# micron_P8.net
KiCad netlist of a schematic drawn in Altium Designer
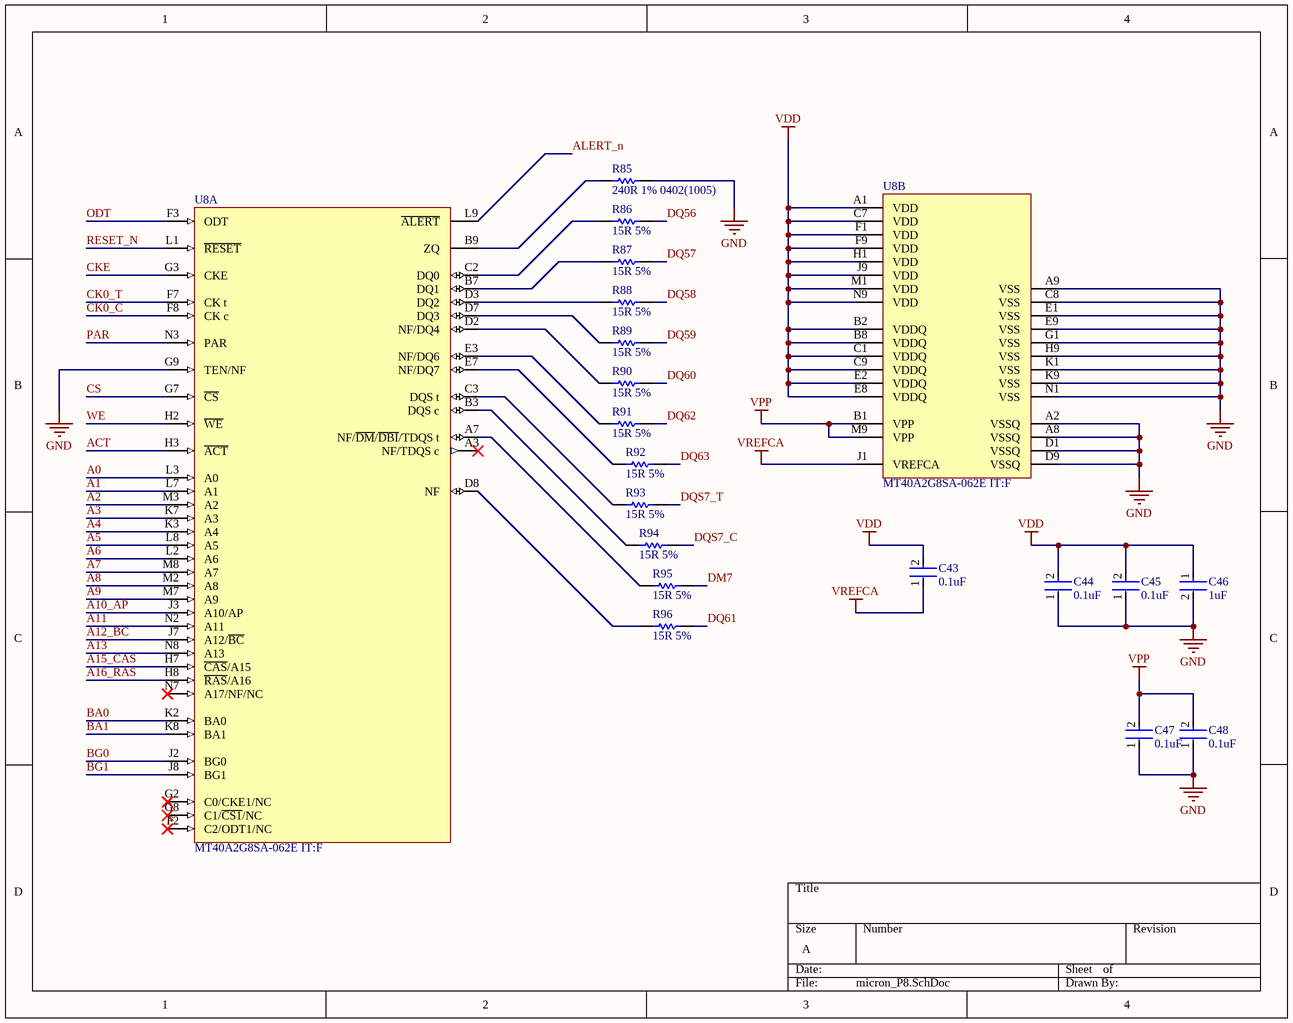
[diagram p0: micron_P8.SchDoc]

(export (version "E")
  (design (tool "Eeschema 10.0.6"))
  (components
    (comp (ref "C43")
      (value "0.1uF")
      (footprint "FP-GRM15-MFG")
      (description "CAP CER 0.1UF 16V X7R 0402")
      (fields (field (name "MANUFACTURER PART NUMBER") "GRM155R71C104KA88D") (field (name "TOLERANCE") "10%"))
      (libsource (lib "Altium Content Vault") (part "236180d848d6139a670b325ea6854c9"))
    )
    (comp (ref "C44")
      (value "0.1uF")
      (footprint "FP-GRM15-MFG")
      (description "CAP CER 0.1UF 16V X7R 0402")
      (fields (field (name "MANUFACTURER PART NUMBER") "GRM155R71C104KA88D") (field (name "TOLERANCE") "10%"))
      (libsource (lib "Altium Content Vault") (part "236180d848d6139a670b325ea6854c9"))
    )
    (comp (ref "C45")
      (value "0.1uF")
      (footprint "FP-GRM15-MFG")
      (description "CAP CER 0.1UF 16V X7R 0402")
      (fields (field (name "MANUFACTURER PART NUMBER") "GRM155R71C104KA88D") (field (name "TOLERANCE") "10%"))
      (libsource (lib "Altium Content Vault") (part "236180d848d6139a670b325ea6854c9"))
    )
    (comp (ref "C46")
      (value "1uF")
      (footprint "FP-CL511-IPC_C")
      (description "Cap Ceramic 1uF 10V X5R ±10% SMD 0402 +85°C Paper T/R")
      (fields (field (name "TOLERANCE") "10%"))
      (libsource (lib "Altium Content Vault") (part "b4654b650e69147ec39a6b967a45e02"))
    )
    (comp (ref "C47")
      (value "0.1uF")
      (footprint "FP-GRM15-MFG")
      (description "CAP CER 0.1UF 16V X7R 0402")
      (fields (field (name "MANUFACTURER PART NUMBER") "GRM155R71C104KA88D") (field (name "TOLERANCE") "10%"))
      (libsource (lib "Altium Content Vault") (part "236180d848d6139a670b325ea6854c9"))
    )
    (comp (ref "C48")
      (value "0.1uF")
      (footprint "FP-GRM15-MFG")
      (description "CAP CER 0.1UF 16V X7R 0402")
      (fields (field (name "MANUFACTURER PART NUMBER") "GRM155R71C104KA88D") (field (name "TOLERANCE") "10%"))
      (libsource (lib "Altium Content Vault") (part "236180d848d6139a670b325ea6854c9"))
    )
    (comp (ref "R85")
      (value "240R 1% 0402(1005)")
      (footprint "RESC0402(1005)_L")
      (description "240R 0.063W 1% 0402 (1005 Metric)  SMD")
      (fields (field (name "POWER") "0.063 W") (field (name "TOLERANCE") "1 %"))
      (libsource (lib "Altium Content Vault") (part "RES"))
    )
    (comp (ref "R86")
      (value "15R 5%")
      (footprint "RESC1005X40X25LL05T10")
      (fields (field (name "MANUFACTURER") "Yageo / Phycomp") (field (name "PART NUMBER") "RC0402FR-0715RL"))
      (libsource (lib "Altium Content Vault") (part "RES"))
    )
    (comp (ref "R87")
      (value "15R 5%")
      (footprint "RESC1005X40X25LL05T10")
      (fields (field (name "MANUFACTURER") "Yageo / Phycomp") (field (name "PART NUMBER") "RC0402FR-0715RL"))
      (libsource (lib "Altium Content Vault") (part "RES"))
    )
    (comp (ref "R88")
      (value "15R 5%")
      (footprint "RESC1005X40X25LL05T10")
      (fields (field (name "MANUFACTURER") "Yageo / Phycomp") (field (name "PART NUMBER") "RC0402FR-0715RL"))
      (libsource (lib "Altium Content Vault") (part "RES"))
    )
    (comp (ref "R89")
      (value "15R 5%")
      (footprint "RESC1005X40X25LL05T10")
      (fields (field (name "MANUFACTURER") "Yageo / Phycomp") (field (name "PART NUMBER") "RC0402FR-0715RL"))
      (libsource (lib "Altium Content Vault") (part "RES"))
    )
    (comp (ref "R90")
      (value "15R 5%")
      (footprint "RESC1005X40X25LL05T10")
      (fields (field (name "MANUFACTURER") "Yageo / Phycomp") (field (name "PART NUMBER") "RC0402FR-0715RL"))
      (libsource (lib "Altium Content Vault") (part "RES"))
    )
    (comp (ref "R91")
      (value "15R 5%")
      (footprint "RESC1005X40X25LL05T10")
      (fields (field (name "MANUFACTURER") "Yageo / Phycomp") (field (name "PART NUMBER") "RC0402FR-0715RL"))
      (libsource (lib "Altium Content Vault") (part "RES"))
    )
    (comp (ref "R92")
      (value "15R 5%")
      (footprint "RESC1005X40X25LL05T10")
      (fields (field (name "MANUFACTURER") "Yageo / Phycomp") (field (name "PART NUMBER") "RC0402FR-0715RL"))
      (libsource (lib "Altium Content Vault") (part "RES"))
    )
    (comp (ref "R93")
      (value "15R 5%")
      (footprint "RESC1005X40X25LL05T10")
      (fields (field (name "MANUFACTURER") "Yageo / Phycomp") (field (name "PART NUMBER") "RC0402FR-0715RL"))
      (libsource (lib "Altium Content Vault") (part "RES"))
    )
    (comp (ref "R94")
      (value "15R 5%")
      (footprint "RESC1005X40X25LL05T10")
      (fields (field (name "MANUFACTURER") "Yageo / Phycomp") (field (name "PART NUMBER") "RC0402FR-0715RL"))
      (libsource (lib "Altium Content Vault") (part "RES"))
    )
    (comp (ref "R95")
      (value "15R 5%")
      (footprint "RESC1005X40X25LL05T10")
      (fields (field (name "MANUFACTURER") "Yageo / Phycomp") (field (name "PART NUMBER") "RC0402FR-0715RL"))
      (libsource (lib "Altium Content Vault") (part "RES"))
    )
    (comp (ref "R96")
      (value "15R 5%")
      (footprint "RESC1005X40X25LL05T10")
      (fields (field (name "MANUFACTURER") "Yageo / Phycomp") (field (name "PART NUMBER") "RC0402FR-0715RL"))
      (libsource (lib "Altium Content Vault") (part "RES"))
    )
    (comp (ref "U8")
      (value "MT40A2G8SA-062E IT:F")
      (footprint "SA_MFG")
      (description "DRAMChip DDR4 SDRAM 16Gbit 2Gx8 1.2V 78-Pin FBGA Tray")
      (libsource (lib "Altium Content Vault") (part "d28cb998757b614ee3280f10a38a3b1"))
    )
  )
  (nets
    (net (code "1") (name "/A0") (class "Default")
      (node (ref "U8") (pin "L3") (pinfunction "A0_L3") (pintype "input"))
    )
    (net (code "2") (name "/A1") (class "Default")
      (node (ref "U8") (pin "L7") (pinfunction "A1_L7") (pintype "input"))
    )
    (net (code "3") (name "/A2") (class "Default")
      (node (ref "U8") (pin "M3") (pinfunction "A2_M3") (pintype "input"))
    )
    (net (code "4") (name "/A3") (class "Default")
      (node (ref "U8") (pin "K7") (pinfunction "A3_K7") (pintype "input"))
    )
    (net (code "5") (name "/A4") (class "Default")
      (node (ref "U8") (pin "K3") (pinfunction "A4_K3") (pintype "input"))
    )
    (net (code "6") (name "/A5") (class "Default")
      (node (ref "U8") (pin "L8") (pinfunction "A5_L8") (pintype "input"))
    )
    (net (code "7") (name "/A6") (class "Default")
      (node (ref "U8") (pin "L2") (pinfunction "A6_L2") (pintype "input"))
    )
    (net (code "8") (name "/A7") (class "Default")
      (node (ref "U8") (pin "M8") (pinfunction "A7_M8") (pintype "input"))
    )
    (net (code "9") (name "/A8") (class "Default")
      (node (ref "U8") (pin "M2") (pinfunction "A8_M2") (pintype "input"))
    )
    (net (code "10") (name "/A9") (class "Default")
      (node (ref "U8") (pin "M7") (pinfunction "A9_M7") (pintype "input"))
    )
    (net (code "11") (name "/A10_AP") (class "Default")
      (node (ref "U8") (pin "J3") (pinfunction "A10/AP_J3") (pintype "input"))
    )
    (net (code "12") (name "/A11") (class "Default")
      (node (ref "U8") (pin "N2") (pinfunction "A11_N2") (pintype "input"))
    )
    (net (code "13") (name "/A12_BC") (class "Default")
      (node (ref "U8") (pin "J7") (pinfunction "A12/~{BC}_J7") (pintype "input"))
    )
    (net (code "14") (name "/A13") (class "Default")
      (node (ref "U8") (pin "N8") (pinfunction "A13_N8") (pintype "input"))
    )
    (net (code "15") (name "/A15_CAS") (class "Default")
      (node (ref "U8") (pin "H7") (pinfunction "~{CAS}/A15_H7") (pintype "input"))
    )
    (net (code "16") (name "/A16_RAS") (class "Default")
      (node (ref "U8") (pin "H8") (pinfunction "~{RAS}/A16_H8") (pintype "input"))
    )
    (net (code "17") (name "/ACT") (class "Default")
      (node (ref "U8") (pin "H3") (pinfunction "~{ACT}_H3") (pintype "input"))
    )
    (net (code "18") (name "/ALERT_n") (class "Default")
      (node (ref "U8") (pin "L9") (pinfunction "~{ALERT}_L9") (pintype "open_collector"))
    )
    (net (code "19") (name "/BA0") (class "Default")
      (node (ref "U8") (pin "K2") (pinfunction "BA0_K2") (pintype "input"))
    )
    (net (code "20") (name "/BA1") (class "Default")
      (node (ref "U8") (pin "K8") (pinfunction "BA1_K8") (pintype "input"))
    )
    (net (code "21") (name "/BG0") (class "Default")
      (node (ref "U8") (pin "J2") (pinfunction "BG0_J2") (pintype "input"))
    )
    (net (code "22") (name "/BG1") (class "Default")
      (node (ref "U8") (pin "J8") (pinfunction "BG1_J8") (pintype "input"))
    )
    (net (code "23") (name "/CK0_C") (class "Default")
      (node (ref "U8") (pin "F8") (pinfunction "CK_c_F8") (pintype "input"))
    )
    (net (code "24") (name "/CK0_T") (class "Default")
      (node (ref "U8") (pin "F7") (pinfunction "CK_t_F7") (pintype "input"))
    )
    (net (code "25") (name "/CKE") (class "Default")
      (node (ref "U8") (pin "G3") (pinfunction "CKE_G3") (pintype "input"))
    )
    (net (code "26") (name "/CS") (class "Default")
      (node (ref "U8") (pin "G7") (pinfunction "~{CS}_G7") (pintype "input"))
    )
    (net (code "27") (name "/DM7") (class "Default")
      (node (ref "R95") (pin "2") (pinfunction "2_2") (pintype "passive"))
    )
    (net (code "28") (name "/DQ56") (class "Default")
      (node (ref "R86") (pin "2") (pinfunction "2_2") (pintype "passive"))
    )
    (net (code "29") (name "/DQ57") (class "Default")
      (node (ref "R87") (pin "2") (pinfunction "2_2") (pintype "passive"))
    )
    (net (code "30") (name "/DQ58") (class "Default")
      (node (ref "R88") (pin "2") (pinfunction "2_2") (pintype "passive"))
    )
    (net (code "31") (name "/DQ59") (class "Default")
      (node (ref "R89") (pin "2") (pinfunction "2_2") (pintype "passive"))
    )
    (net (code "32") (name "/DQ60") (class "Default")
      (node (ref "R90") (pin "2") (pinfunction "2_2") (pintype "passive"))
    )
    (net (code "33") (name "/DQ61") (class "Default")
      (node (ref "R96") (pin "2") (pinfunction "2_2") (pintype "passive"))
    )
    (net (code "34") (name "/DQ62") (class "Default")
      (node (ref "R91") (pin "2") (pinfunction "2_2") (pintype "passive"))
    )
    (net (code "35") (name "/DQ63") (class "Default")
      (node (ref "R92") (pin "2") (pinfunction "2_2") (pintype "passive"))
    )
    (net (code "36") (name "/DQS7_C") (class "Default")
      (node (ref "R94") (pin "2") (pinfunction "2_2") (pintype "passive"))
    )
    (net (code "37") (name "/DQS7_T") (class "Default")
      (node (ref "R93") (pin "2") (pinfunction "2_2") (pintype "passive"))
    )
    (net (code "38") (name "/ODT") (class "Default")
      (node (ref "U8") (pin "F3") (pinfunction "ODT_F3") (pintype "input"))
    )
    (net (code "39") (name "/PAR") (class "Default")
      (node (ref "U8") (pin "N3") (pinfunction "PAR_N3") (pintype "input"))
    )
    (net (code "40") (name "/RESET_N") (class "Default")
      (node (ref "U8") (pin "L1") (pinfunction "~{RESET}_L1") (pintype "input"))
    )
    (net (code "41") (name "/WE") (class "Default")
      (node (ref "U8") (pin "H2") (pinfunction "~{WE}_H2") (pintype "input"))
    )
    (net (code "42") (name "GND") (class "Default")
      (node (ref "C44") (pin "1") (pinfunction "1_1") (pintype "passive"))
      (node (ref "C45") (pin "1") (pinfunction "1_1") (pintype "passive"))
      (node (ref "C46") (pin "2") (pinfunction "2_2") (pintype "passive"))
      (node (ref "C47") (pin "1") (pinfunction "1_1") (pintype "passive"))
      (node (ref "C48") (pin "1") (pinfunction "1_1") (pintype "passive"))
      (node (ref "R85") (pin "2") (pinfunction "2_2") (pintype "passive"))
      (node (ref "U8") (pin "A2") (pinfunction "VSSQ_A2") (pintype "power_in"))
      (node (ref "U8") (pin "A8") (pinfunction "VSSQ_A8") (pintype "power_in"))
      (node (ref "U8") (pin "A9") (pinfunction "VSS_A9") (pintype "power_in"))
      (node (ref "U8") (pin "C8") (pinfunction "VSS_C8") (pintype "power_in"))
      (node (ref "U8") (pin "D1") (pinfunction "VSSQ_D1") (pintype "power_in"))
      (node (ref "U8") (pin "D9") (pinfunction "VSSQ_D9") (pintype "power_in"))
      (node (ref "U8") (pin "E1") (pinfunction "VSS_E1") (pintype "power_in"))
      (node (ref "U8") (pin "E9") (pinfunction "VSS_E9") (pintype "power_in"))
      (node (ref "U8") (pin "G1") (pinfunction "VSS_G1") (pintype "power_in"))
      (node (ref "U8") (pin "G9") (pinfunction "TEN/NF_G9") (pintype "input"))
      (node (ref "U8") (pin "H9") (pinfunction "VSS_H9") (pintype "power_in"))
      (node (ref "U8") (pin "K1") (pinfunction "VSS_K1") (pintype "power_in"))
      (node (ref "U8") (pin "K9") (pinfunction "VSS_K9") (pintype "power_in"))
      (node (ref "U8") (pin "N1") (pinfunction "VSS_N1") (pintype "power_in"))
    )
    (net (code "43") (name "Net-(U8A-DQ0)") (class "Default")
      (node (ref "R86") (pin "1") (pinfunction "1_1") (pintype "passive"))
      (node (ref "U8") (pin "C2") (pinfunction "DQ0_C2") (pintype "bidirectional"))
    )
    (net (code "44") (name "Net-(U8A-DQ1)") (class "Default")
      (node (ref "R87") (pin "1") (pinfunction "1_1") (pintype "passive"))
      (node (ref "U8") (pin "B7") (pinfunction "DQ1_B7") (pintype "bidirectional"))
    )
    (net (code "45") (name "Net-(U8A-DQ2)") (class "Default")
      (node (ref "R88") (pin "1") (pinfunction "1_1") (pintype "passive"))
      (node (ref "U8") (pin "D3") (pinfunction "DQ2_D3") (pintype "bidirectional"))
    )
    (net (code "46") (name "Net-(U8A-DQ3)") (class "Default")
      (node (ref "R89") (pin "1") (pinfunction "1_1") (pintype "passive"))
      (node (ref "U8") (pin "D7") (pinfunction "DQ3_D7") (pintype "bidirectional"))
    )
    (net (code "47") (name "Net-(U8A-DQS_c)") (class "Default")
      (node (ref "R94") (pin "1") (pinfunction "1_1") (pintype "passive"))
      (node (ref "U8") (pin "B3") (pinfunction "DQS_c_B3") (pintype "bidirectional"))
    )
    (net (code "48") (name "Net-(U8A-DQS_t)") (class "Default")
      (node (ref "R93") (pin "1") (pinfunction "1_1") (pintype "passive"))
      (node (ref "U8") (pin "C3") (pinfunction "DQS_t_C3") (pintype "bidirectional"))
    )
    (net (code "49") (name "Net-(U8A-NF)") (class "Default")
      (node (ref "R96") (pin "1") (pinfunction "1_1") (pintype "passive"))
      (node (ref "U8") (pin "D8") (pinfunction "NF_D8") (pintype "bidirectional"))
    )
    (net (code "50") (name "Net-(U8A-NF{slash}DQ4)") (class "Default")
      (node (ref "R90") (pin "1") (pinfunction "1_1") (pintype "passive"))
      (node (ref "U8") (pin "D2") (pinfunction "NF/DQ4_D2") (pintype "bidirectional"))
    )
    (net (code "51") (name "Net-(U8A-NF{slash}DQ6)") (class "Default")
      (node (ref "R91") (pin "1") (pinfunction "1_1") (pintype "passive"))
      (node (ref "U8") (pin "E3") (pinfunction "NF/DQ6_E3") (pintype "bidirectional"))
    )
    (net (code "52") (name "Net-(U8A-NF{slash}DQ7)") (class "Default")
      (node (ref "R92") (pin "1") (pinfunction "1_1") (pintype "passive"))
      (node (ref "U8") (pin "E7") (pinfunction "NF/DQ7_E7") (pintype "bidirectional"))
    )
    (net (code "53") (name "Net-(U8A-NF{slash}~{DM}{slash}~{DBI}{slash}TDQS_t)") (class "Default")
      (node (ref "R95") (pin "1") (pinfunction "1_1") (pintype "passive"))
      (node (ref "U8") (pin "A7") (pinfunction "NF/~{DM}/~{DBI}/TDQS_t_A7") (pintype "bidirectional"))
    )
    (net (code "54") (name "Net-(U8A-ZQ)") (class "Default")
      (node (ref "R85") (pin "1") (pinfunction "1_1") (pintype "passive"))
      (node (ref "U8") (pin "B9") (pinfunction "ZQ_B9") (pintype "passive"))
    )
    (net (code "55") (name "VDD") (class "Default")
      (node (ref "C43") (pin "2") (pinfunction "2_2") (pintype "passive"))
      (node (ref "C44") (pin "2") (pinfunction "2_2") (pintype "passive"))
      (node (ref "C45") (pin "2") (pinfunction "2_2") (pintype "passive"))
      (node (ref "C46") (pin "1") (pinfunction "1_1") (pintype "passive"))
      (node (ref "U8") (pin "A1") (pinfunction "VDD_A1") (pintype "power_in"))
      (node (ref "U8") (pin "B2") (pinfunction "VDDQ_B2") (pintype "power_in"))
      (node (ref "U8") (pin "B8") (pinfunction "VDDQ_B8") (pintype "power_in"))
      (node (ref "U8") (pin "C1") (pinfunction "VDDQ_C1") (pintype "power_in"))
      (node (ref "U8") (pin "C7") (pinfunction "VDD_C7") (pintype "power_in"))
      (node (ref "U8") (pin "C9") (pinfunction "VDDQ_C9") (pintype "power_in"))
      (node (ref "U8") (pin "E2") (pinfunction "VDDQ_E2") (pintype "power_in"))
      (node (ref "U8") (pin "E8") (pinfunction "VDDQ_E8") (pintype "power_in"))
      (node (ref "U8") (pin "F1") (pinfunction "VDD_F1") (pintype "power_in"))
      (node (ref "U8") (pin "F9") (pinfunction "VDD_F9") (pintype "power_in"))
      (node (ref "U8") (pin "H1") (pinfunction "VDD_H1") (pintype "power_in"))
      (node (ref "U8") (pin "J9") (pinfunction "VDD_J9") (pintype "power_in"))
      (node (ref "U8") (pin "M1") (pinfunction "VDD_M1") (pintype "power_in"))
      (node (ref "U8") (pin "N9") (pinfunction "VDD_N9") (pintype "power_in"))
    )
    (net (code "56") (name "VPP") (class "Default")
      (node (ref "C47") (pin "2") (pinfunction "2_2") (pintype "passive"))
      (node (ref "C48") (pin "2") (pinfunction "2_2") (pintype "passive"))
      (node (ref "U8") (pin "B1") (pinfunction "VPP_B1") (pintype "power_in"))
      (node (ref "U8") (pin "M9") (pinfunction "VPP_M9") (pintype "power_in"))
    )
    (net (code "57") (name "VREFCA") (class "Default")
      (node (ref "C43") (pin "1") (pinfunction "1_1") (pintype "passive"))
      (node (ref "U8") (pin "J1") (pinfunction "VREFCA_J1") (pintype "power_in"))
    )
    (net (code "58") (name "unconnected-(U8A-A17{slash}NF{slash}NC-PadN7)") (class "Default")
      (node (ref "U8") (pin "N7") (pinfunction "A17/NF/NC_N7") (pintype "input+no_connect"))
    )
    (net (code "59") (name "unconnected-(U8A-C0{slash}CKE1{slash}NC-PadG2)") (class "Default")
      (node (ref "U8") (pin "G2") (pinfunction "C0/CKE1/NC_G2") (pintype "input+no_connect"))
    )
    (net (code "60") (name "unconnected-(U8A-C1{slash}~{CS1}{slash}NC-PadG8)") (class "Default")
      (node (ref "U8") (pin "G8") (pinfunction "C1/~{CS1}/NC_G8") (pintype "input+no_connect"))
    )
    (net (code "61") (name "unconnected-(U8A-C2{slash}ODT1{slash}NC-PadF2)") (class "Default")
      (node (ref "U8") (pin "F2") (pinfunction "C2/ODT1/NC_F2") (pintype "input+no_connect"))
    )
    (net (code "62") (name "unconnected-(U8A-NF{slash}TDQS_c-PadA3)") (class "Default")
      (node (ref "U8") (pin "A3") (pinfunction "NF/TDQS_c_A3") (pintype "output+no_connect"))
    )
  )
)
